# SNES_TST_Sheet4.net
KiCad netlist of a schematic drawn in Altium Designer
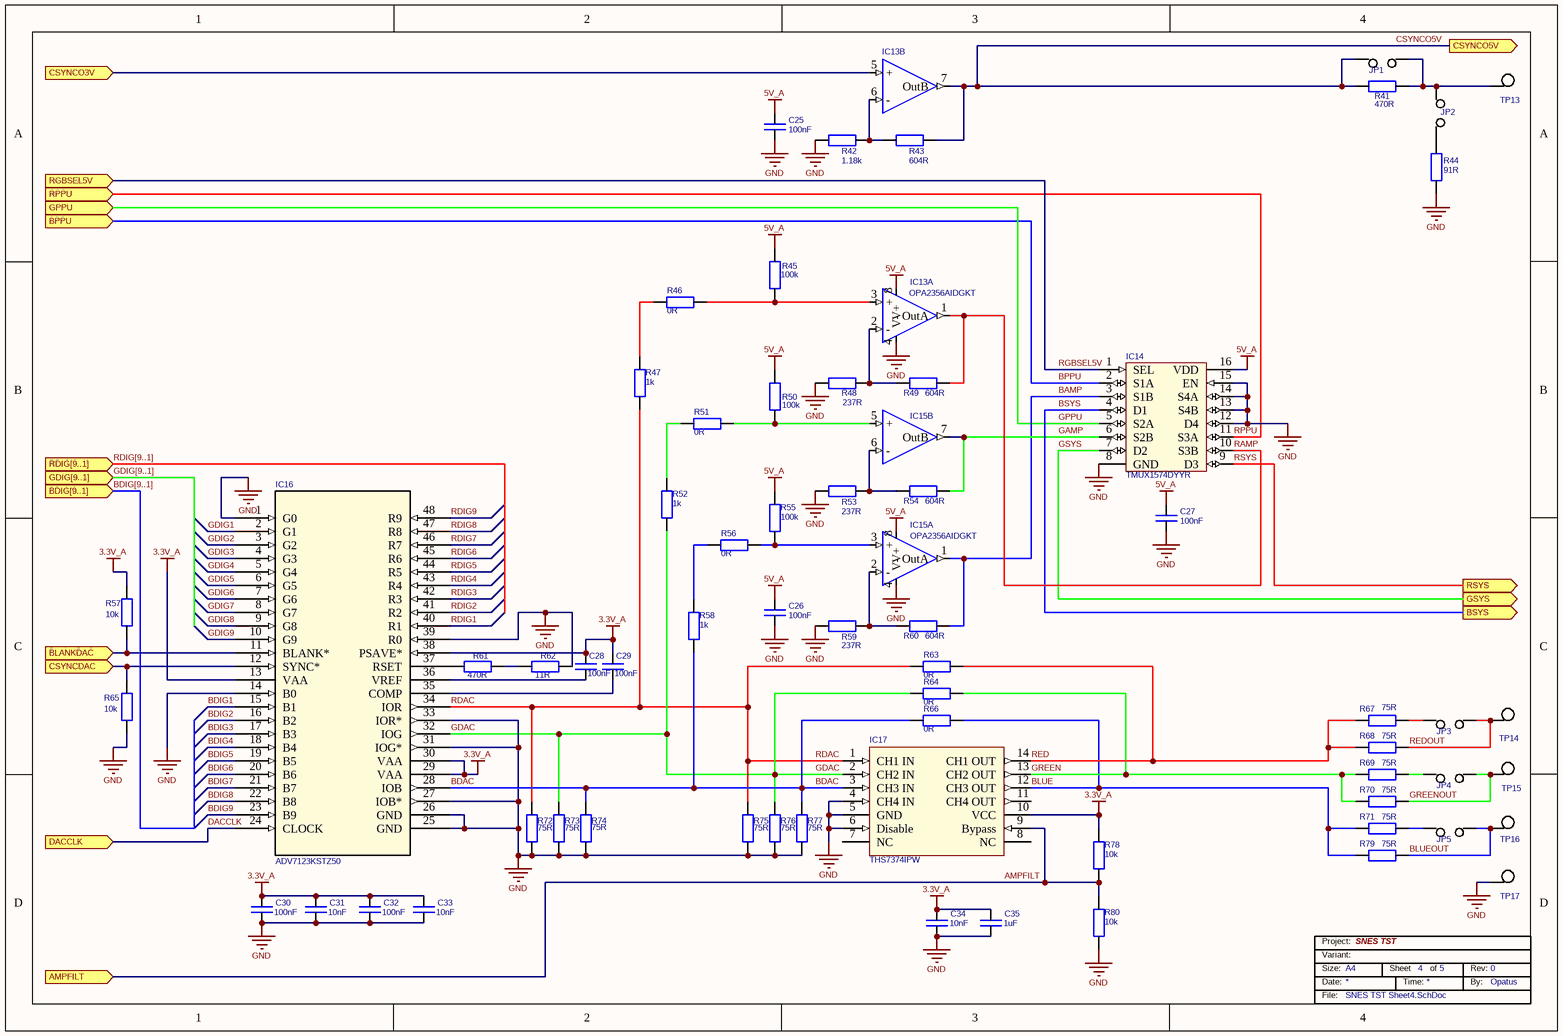
[diagram p0: SNES TST Sheet4.SchDoc]

(export (version "E")
  (design (tool "Eeschema 10.0.6"))
  (components
    (comp (ref "C25")
      (value "100nF")
      (footprint "Cap_0402_Chip")
      (fields
        (field (name "TOLERANCE") "±20%")
        (field (name "Comment") "Ceramic Capacitor 100nF 10V ±20% X7R 0402")
      )
      (libsource (lib "PCB") (part "Capacitor"))
    )
    (comp (ref "C26")
      (value "100nF")
      (footprint "Cap_0402_Chip")
      (fields
        (field (name "TOLERANCE") "±20%")
        (field (name "Comment") "Ceramic Capacitor 100nF 10V ±20% X7R 0402")
      )
      (libsource (lib "PCB") (part "Capacitor"))
    )
    (comp (ref "C27")
      (value "100nF")
      (footprint "Cap_0402_Chip")
      (fields
        (field (name "TOLERANCE") "±20%")
        (field (name "Comment") "Ceramic Capacitor 100nF 10V ±20% X7R 0402")
      )
      (libsource (lib "PCB") (part "Capacitor"))
    )
    (comp (ref "C28")
      (value "100nF")
      (footprint "Cap_0402_Chip")
      (fields
        (field (name "TOLERANCE") "±20%")
        (field (name "Comment") "Ceramic Capacitor 100nF 10V ±20% X7R 0402")
      )
      (libsource (lib "PCB") (part "Capacitor"))
    )
    (comp (ref "C29")
      (value "100nF")
      (footprint "Cap_0402_Chip")
      (fields
        (field (name "TOLERANCE") "±20%")
        (field (name "Comment") "Ceramic Capacitor 100nF 10V ±20% X7R 0402")
      )
      (libsource (lib "PCB") (part "Capacitor"))
    )
    (comp (ref "C30")
      (value "100nF")
      (footprint "Cap_0402_Chip")
      (fields
        (field (name "TOLERANCE") "±20%")
        (field (name "Comment") "Ceramic Capacitor 100nF 10V ±20% X7R 0402")
      )
      (libsource (lib "PCB") (part "Capacitor"))
    )
    (comp (ref "C31")
      (value "10nF")
      (footprint "Cap_0402_Chip")
      (fields
        (field (name "TOLERANCE") "±20%")
        (field (name "Comment") "Ceramic Capacitor 10nF 10V ±20% X7R 0402")
      )
      (libsource (lib "PCB") (part "Capacitor"))
    )
    (comp (ref "C32")
      (value "100nF")
      (footprint "Cap_0402_Chip")
      (fields
        (field (name "TOLERANCE") "±20%")
        (field (name "Comment") "Ceramic Capacitor 100nF 10V ±20% X7R 0402")
      )
      (libsource (lib "PCB") (part "Capacitor"))
    )
    (comp (ref "C33")
      (value "10nF")
      (footprint "Cap_0402_Chip")
      (fields
        (field (name "TOLERANCE") "±20%")
        (field (name "Comment") "Ceramic Capacitor 10nF 10V ±20% X7R 0402")
      )
      (libsource (lib "PCB") (part "Capacitor"))
    )
    (comp (ref "C34")
      (value "10nF")
      (footprint "Cap_0402_Chip")
      (fields
        (field (name "TOLERANCE") "±20%")
        (field (name "Comment") "Ceramic Capacitor 10nF 10V ±20% X7R 0402")
      )
      (libsource (lib "PCB") (part "Capacitor"))
    )
    (comp (ref "C35")
      (value "1uF")
      (footprint "Cap_0603_Chip")
      (fields
        (field (name "TOLERANCE") "±20%")
        (field (name "Comment") "Ceramic Capacitor 1uF 10V ±20% X7R 0603")
      )
      (libsource (lib "PCB") (part "Capacitor"))
    )
    (comp (ref "IC13")
      (value "OPA2356")
      (footprint "MSOP8")
      (fields (field (name "MANUFACTURER_PART_NUMBER") "OPA2356AIDGKT"))
      (libsource (lib "PCB") (part "OPA2356"))
    )
    (comp (ref "IC14")
      (value "TMUX1574")
      (footprint "SOT-23THIN16")
      (description "SPDT 4 Ch")
      (fields (field (name "MANUFACTURER_PART_NUMBER") "TMUX1574DYYR"))
      (libsource (lib "PCB") (part "TMUX1574"))
    )
    (comp (ref "IC15")
      (value "OPA2356")
      (footprint "MSOP8")
      (fields (field (name "MANUFACTURER_PART_NUMBER") "OPA2356AIDGKT"))
      (libsource (lib "PCB") (part "OPA2356"))
    )
    (comp (ref "IC16")
      (value "ADV7123")
      (footprint "ST_48_ADI")
      (description "10Bit Video DAC")
      (fields
        (field (name "MANUFACTURER_PART_NUMBER") "ADV7123KSTZ50")
        (field (name "COPYRIGHT") "Copyright (C) 2018 Accelerated Designs. All rights reserved")
      )
      (libsource (lib "PCB") (part "ADV7123KSTZ140"))
    )
    (comp (ref "IC17")
      (value "THS7374")
      (footprint "TSSOP14")
      (fields (field (name "MANUFACTURER_PART_NUMBER") "THS7374IPW"))
      (libsource (lib "PCB") (part "THS7374"))
    )
    (comp (ref "JP1") (value "Jumper") (footprint "Jumper") (libsource (lib "PCB") (part "Jumper")))
    (comp (ref "JP2") (value "Jumper") (footprint "Jumper") (libsource (lib "PCB") (part "Jumper")))
    (comp (ref "JP3") (value "Jumper") (footprint "Jumper") (libsource (lib "PCB") (part "Jumper")))
    (comp (ref "JP4") (value "Jumper") (footprint "Jumper") (libsource (lib "PCB") (part "Jumper")))
    (comp (ref "JP5") (value "Jumper") (footprint "Jumper") (libsource (lib "PCB") (part "Jumper")))
    (comp (ref "R41")
      (value "470R")
      (footprint "Res_0603_Chip")
      (fields (field (name "TOLERANCE") "±1%") (field (name "Comment") "Resistor 470R 0603 ±1%"))
      (libsource (lib "PCB") (part "R"))
    )
    (comp (ref "R42")
      (value "1.18k")
      (footprint "Res_0402_Chip")
      (fields (field (name "TOLERANCE") "±1%") (field (name "Comment") "Resistor 1.18k 0402 ±1%"))
      (libsource (lib "PCB") (part "R"))
    )
    (comp (ref "R43")
      (value "604R")
      (footprint "Res_0402_Chip")
      (fields (field (name "TOLERANCE") "±1%") (field (name "Comment") "Resistor 604R 0402 ±1%"))
      (libsource (lib "") (part "R_2"))
    )
    (comp (ref "R44")
      (value "91R")
      (footprint "Res_0603_Chip")
      (fields (field (name "TOLERANCE") "±1%") (field (name "Comment") "Resistor 91R 0603 ±1%"))
      (libsource (lib "") (part "R_1"))
    )
    (comp (ref "R45")
      (value "100k")
      (footprint "Res_0402_Chip")
      (fields (field (name "TOLERANCE") "±1%") (field (name "Comment") "Resistor 100k 0402 ±1%"))
      (libsource (lib "") (part "R_1"))
    )
    (comp (ref "R46")
      (value "0R")
      (footprint "Res_0402_Chip")
      (fields (field (name "Comment") "Resistor 0R 0402 "))
      (libsource (lib "") (part "R_2"))
    )
    (comp (ref "R47")
      (value "1k")
      (footprint "Res_0402_Chip")
      (fields (field (name "TOLERANCE") "±1%") (field (name "Comment") "Resistor 1k 0402 ±1%"))
      (libsource (lib "") (part "R_3"))
    )
    (comp (ref "R48")
      (value "237R")
      (footprint "Res_0402_Chip")
      (fields (field (name "TOLERANCE") "±1%") (field (name "Comment") "Resistor 237R 0402 ±1%"))
      (libsource (lib "PCB") (part "R"))
    )
    (comp (ref "R49")
      (value "604R")
      (footprint "Res_0402_Chip")
      (fields (field (name "TOLERANCE") "±1%") (field (name "Comment") "Resistor 604R 0402 ±1%"))
      (libsource (lib "PCB") (part "R"))
    )
    (comp (ref "R50")
      (value "100k")
      (footprint "Res_0402_Chip")
      (fields (field (name "TOLERANCE") "±1%") (field (name "Comment") "Resistor 100k 0402 ±1%"))
      (libsource (lib "") (part "R_1"))
    )
    (comp (ref "R51")
      (value "0R")
      (footprint "Res_0402_Chip")
      (fields (field (name "Comment") "Resistor 0R 0402 "))
      (libsource (lib "") (part "R_2"))
    )
    (comp (ref "R52")
      (value "1k")
      (footprint "Res_0402_Chip")
      (fields (field (name "TOLERANCE") "±1%") (field (name "Comment") "Resistor 1k 0402 ±1%"))
      (libsource (lib "") (part "R_3"))
    )
    (comp (ref "R53")
      (value "237R")
      (footprint "Res_0402_Chip")
      (fields (field (name "TOLERANCE") "±1%") (field (name "Comment") "Resistor 237R 0402 ±1%"))
      (libsource (lib "PCB") (part "R"))
    )
    (comp (ref "R54")
      (value "604R")
      (footprint "Res_0402_Chip")
      (fields (field (name "TOLERANCE") "±1%") (field (name "Comment") "Resistor 604R 0402 ±1%"))
      (libsource (lib "") (part "R_2"))
    )
    (comp (ref "R55")
      (value "100k")
      (footprint "Res_0402_Chip")
      (fields (field (name "TOLERANCE") "±1%") (field (name "Comment") "Resistor 100k 0402 ±1%"))
      (libsource (lib "") (part "R_1"))
    )
    (comp (ref "R56")
      (value "0R")
      (footprint "Res_0402_Chip")
      (fields (field (name "Comment") "Resistor 0R 0402 "))
      (libsource (lib "") (part "R_2"))
    )
    (comp (ref "R57")
      (value "10k")
      (footprint "Res_0402_Chip")
      (fields (field (name "TOLERANCE") "±1%") (field (name "Comment") "Resistor 10k 0402 ±1%"))
      (libsource (lib "") (part "R_1"))
    )
    (comp (ref "R58")
      (value "1k")
      (footprint "Res_0402_Chip")
      (fields (field (name "TOLERANCE") "±1%") (field (name "Comment") "Resistor 1k 0402 ±1%"))
      (libsource (lib "") (part "R_3"))
    )
    (comp (ref "R59")
      (value "237R")
      (footprint "Res_0402_Chip")
      (fields (field (name "TOLERANCE") "±1%") (field (name "Comment") "Resistor 237R 0402 ±1%"))
      (libsource (lib "") (part "R_2"))
    )
    (comp (ref "R60")
      (value "604R")
      (footprint "Res_0402_Chip")
      (fields (field (name "TOLERANCE") "±1%") (field (name "Comment") "Resistor 604R 0402 ±1%"))
      (libsource (lib "PCB") (part "R"))
    )
    (comp (ref "R61")
      (value "470R")
      (footprint "Res_0402_Chip")
      (fields (field (name "TOLERANCE") "±1%") (field (name "Comment") "Resistor 470R 0402 ±1%"))
      (libsource (lib "PCB") (part "R"))
    )
    (comp (ref "R62")
      (value "11R")
      (footprint "Res_0402_Chip")
      (fields (field (name "TOLERANCE") "±1%") (field (name "Comment") "Resistor 11R 0402 ±1%"))
      (libsource (lib "PCB") (part "R"))
    )
    (comp (ref "R63")
      (value "0R")
      (footprint "Res_0402_Chip")
      (fields (field (name "Comment") "Resistor 0R 0402 "))
      (libsource (lib "") (part "R_2"))
    )
    (comp (ref "R64")
      (value "0R")
      (footprint "Res_0402_Chip")
      (fields (field (name "Comment") "Resistor 0R 0402 "))
      (libsource (lib "") (part "R_2"))
    )
    (comp (ref "R65")
      (value "10k")
      (footprint "Res_0402_Chip")
      (fields (field (name "TOLERANCE") "±1%") (field (name "Comment") "Resistor 10k 0402 ±1%"))
      (libsource (lib "") (part "R_1"))
    )
    (comp (ref "R66")
      (value "0R")
      (footprint "Res_0402_Chip")
      (fields (field (name "Comment") "Resistor 0R 0402 "))
      (libsource (lib "") (part "R_2"))
    )
    (comp (ref "R67")
      (value "75R")
      (footprint "Res_0603_Chip")
      (fields (field (name "TOLERANCE") "±1%") (field (name "Comment") "Resistor 75R 0603 ±1%"))
      (libsource (lib "PCB") (part "R"))
    )
    (comp (ref "R68")
      (value "75R")
      (footprint "Res_0603_Chip")
      (fields (field (name "TOLERANCE") "±1%") (field (name "Comment") "Resistor 75R 0603 ±1%"))
      (libsource (lib "PCB") (part "R"))
    )
    (comp (ref "R69")
      (value "75R")
      (footprint "Res_0603_Chip")
      (fields (field (name "TOLERANCE") "±1%") (field (name "Comment") "Resistor 75R 0603 ±1%"))
      (libsource (lib "PCB") (part "R"))
    )
    (comp (ref "R70")
      (value "75R")
      (footprint "Res_0603_Chip")
      (fields (field (name "TOLERANCE") "±1%") (field (name "Comment") "Resistor 75R 0603 ±1%"))
      (libsource (lib "PCB") (part "R"))
    )
    (comp (ref "R71")
      (value "75R")
      (footprint "Res_0603_Chip")
      (fields (field (name "TOLERANCE") "±1%") (field (name "Comment") "Resistor 75R 0603 ±1%"))
      (libsource (lib "PCB") (part "R"))
    )
    (comp (ref "R72")
      (value "75R")
      (footprint "Res_0402_Chip")
      (fields (field (name "TOLERANCE") "±1%") (field (name "Comment") "Resistor 75R 0402 ±1%"))
      (libsource (lib "") (part "R_1"))
    )
    (comp (ref "R73")
      (value "75R")
      (footprint "Res_0402_Chip")
      (fields (field (name "TOLERANCE") "±1%") (field (name "Comment") "Resistor 75R 0402 ±1%"))
      (libsource (lib "") (part "R_1"))
    )
    (comp (ref "R74")
      (value "75R")
      (footprint "Res_0402_Chip")
      (fields (field (name "TOLERANCE") "±1%") (field (name "Comment") "Resistor 75R 0402 ±1%"))
      (libsource (lib "") (part "R_1"))
    )
    (comp (ref "R75")
      (value "75R")
      (footprint "Res_0402_Chip")
      (fields (field (name "TOLERANCE") "±1%") (field (name "Comment") "Resistor 75R 0402 ±1%"))
      (libsource (lib "") (part "R_1"))
    )
    (comp (ref "R76")
      (value "75R")
      (footprint "Res_0402_Chip")
      (fields (field (name "TOLERANCE") "±1%") (field (name "Comment") "Resistor 75R 0402 ±1%"))
      (libsource (lib "") (part "R_1"))
    )
    (comp (ref "R77")
      (value "75R")
      (footprint "Res_0402_Chip")
      (fields (field (name "TOLERANCE") "±1%") (field (name "Comment") "Resistor 75R 0402 ±1%"))
      (libsource (lib "") (part "R_1"))
    )
    (comp (ref "R78")
      (value "10k")
      (footprint "Res_0402_Chip")
      (fields (field (name "TOLERANCE") "±1%") (field (name "Comment") "Resistor 10k 0402 ±1%"))
      (libsource (lib "") (part "R_3"))
    )
    (comp (ref "R79")
      (value "75R")
      (footprint "Res_0603_Chip")
      (fields (field (name "TOLERANCE") "±1%") (field (name "Comment") "Resistor 75R 0603 ±1%"))
      (libsource (lib "PCB") (part "R"))
    )
    (comp (ref "R80")
      (value "10k")
      (footprint "Res_0402_Chip")
      (fields (field (name "TOLERANCE") "±1%") (field (name "Comment") "Resistor 10k 0402 ±1%"))
      (libsource (lib "") (part "R_3"))
    )
    (comp (ref "TP13")
      (value "Pin Connector")
      (footprint "Pin Connector Small")
      (libsource (lib "PCB") (part "Pin Connector"))
    )
    (comp (ref "TP14")
      (value "Pin Connector")
      (footprint "Pin Connector Small")
      (libsource (lib "PCB") (part "Pin Connector"))
    )
    (comp (ref "TP15")
      (value "Pin Connector")
      (footprint "Pin Connector Small")
      (libsource (lib "PCB") (part "Pin Connector"))
    )
    (comp (ref "TP16")
      (value "Pin Connector")
      (footprint "Pin Connector Small")
      (libsource (lib "PCB") (part "Pin Connector"))
    )
    (comp (ref "TP17")
      (value "Pin Connector")
      (footprint "Pin Connector Small")
      (libsource (lib "PCB") (part "Pin Connector"))
    )
  )
  (nets
    (net (code "1") (name "/AMPFILT") (class "Default")
      (node (ref "IC17") (pin "9") (pinfunction "Bypass_9") (pintype "input"))
      (node (ref "R78") (pin "2") (pintype "passive"))
      (node (ref "R80") (pin "1") (pintype "passive"))
    )
    (net (code "2") (name "/BAMP") (class "Default")
      (node (ref "IC14") (pin "3") (pinfunction "S1B_3") (pintype "bidirectional"))
      (node (ref "IC15") (pin "1") (pinfunction "OutA_1") (pintype "output"))
      (node (ref "R60") (pin "2") (pintype "passive"))
    )
    (net (code "3") (name "/BDAC") (class "Default")
      (node (ref "IC16") (pin "28") (pinfunction "IOB_28") (pintype "output"))
      (node (ref "IC17") (pin "3") (pinfunction "CH3_IN_3") (pintype "input"))
      (node (ref "R58") (pin "2") (pintype "passive"))
      (node (ref "R66") (pin "2") (pintype "passive"))
      (node (ref "R74") (pin "2") (pintype "passive"))
      (node (ref "R77") (pin "2") (pintype "passive"))
    )
    (net (code "4") (name "/BDIG1") (class "Default")
      (node (ref "IC16") (pin "15") (pinfunction "B1_15") (pintype "input"))
    )
    (net (code "5") (name "/BDIG2") (class "Default")
      (node (ref "IC16") (pin "16") (pinfunction "B2_16") (pintype "input"))
    )
    (net (code "6") (name "/BDIG3") (class "Default")
      (node (ref "IC16") (pin "17") (pinfunction "B3_17") (pintype "input"))
    )
    (net (code "7") (name "/BDIG4") (class "Default")
      (node (ref "IC16") (pin "18") (pinfunction "B4_18") (pintype "input"))
    )
    (net (code "8") (name "/BDIG5") (class "Default")
      (node (ref "IC16") (pin "19") (pinfunction "B5_19") (pintype "input"))
    )
    (net (code "9") (name "/BDIG6") (class "Default")
      (node (ref "IC16") (pin "20") (pinfunction "B6_20") (pintype "input"))
    )
    (net (code "10") (name "/BDIG7") (class "Default")
      (node (ref "IC16") (pin "21") (pinfunction "B7_21") (pintype "input"))
    )
    (net (code "11") (name "/BDIG8") (class "Default")
      (node (ref "IC16") (pin "22") (pinfunction "B8_22") (pintype "input"))
    )
    (net (code "12") (name "/BDIG9") (class "Default")
      (node (ref "IC16") (pin "23") (pinfunction "B9_23") (pintype "input"))
    )
    (net (code "14") (name "/BLANKDAC") (class "Default")
      (node (ref "IC16") (pin "11") (pinfunction "BLANK*_11") (pintype "input"))
      (node (ref "R57") (pin "1") (pintype "passive"))
    )
    (net (code "15") (name "/BLUE") (class "Default")
      (node (ref "IC17") (pin "12") (pinfunction "CH3_OUT_12") (pintype "output"))
      (node (ref "R66") (pin "1") (pintype "passive"))
      (node (ref "R71") (pin "1") (pintype "passive"))
      (node (ref "R79") (pin "1") (pintype "passive"))
    )
    (net (code "16") (name "/BLUEOUT") (class "Default")
      (node (ref "JP5") (pin "1") (pinfunction "0_1") (pintype "passive"))
      (node (ref "R79") (pin "2") (pintype "passive"))
      (node (ref "TP16") (pin "1") (pinfunction "0_1") (pintype "passive"))
    )
    (net (code "17") (name "/BPPU") (class "Default")
      (node (ref "IC14") (pin "2") (pinfunction "S1A_2") (pintype "bidirectional"))
    )
    (net (code "18") (name "/BSYS") (class "Default")
      (node (ref "IC14") (pin "4") (pinfunction "D1_4") (pintype "bidirectional"))
    )
    (net (code "19") (name "/CSYNCDAC") (class "Default")
      (node (ref "IC16") (pin "12") (pinfunction "SYNC*_12") (pintype "input"))
      (node (ref "R65") (pin "2") (pintype "passive"))
    )
    (net (code "20") (name "/CSYNCO3V") (class "Default")
      (node (ref "IC13") (pin "5") (pinfunction "+_5") (pintype "input"))
    )
    (net (code "21") (name "/CSYNCO5V") (class "Default")
      (node (ref "IC13") (pin "7") (pinfunction "OutB_7") (pintype "output"))
      (node (ref "JP1") (pin "2") (pinfunction "0_2") (pintype "passive"))
      (node (ref "R41") (pin "1") (pintype "passive"))
      (node (ref "R43") (pin "1") (pintype "passive"))
    )
    (net (code "22") (name "/DACCLK") (class "Default")
      (node (ref "IC16") (pin "24") (pinfunction "CLOCK_24") (pintype "input"))
    )
    (net (code "23") (name "/GAMP") (class "Default")
      (node (ref "IC14") (pin "6") (pinfunction "S2B_6") (pintype "bidirectional"))
      (node (ref "IC15") (pin "7") (pinfunction "OutB_7") (pintype "output"))
      (node (ref "R54") (pin "1") (pintype "passive"))
    )
    (net (code "24") (name "/GDAC") (class "Default")
      (node (ref "IC16") (pin "32") (pinfunction "IOG_32") (pintype "output"))
      (node (ref "IC17") (pin "2") (pinfunction "CH2_IN_2") (pintype "input"))
      (node (ref "R52") (pin "2") (pintype "passive"))
      (node (ref "R64") (pin "2") (pintype "passive"))
      (node (ref "R73") (pin "2") (pintype "passive"))
      (node (ref "R76") (pin "2") (pintype "passive"))
    )
    (net (code "25") (name "/GDIG1") (class "Default")
      (node (ref "IC16") (pin "2") (pinfunction "G1_2") (pintype "input"))
    )
    (net (code "26") (name "/GDIG2") (class "Default")
      (node (ref "IC16") (pin "3") (pinfunction "G2_3") (pintype "input"))
    )
    (net (code "27") (name "/GDIG3") (class "Default")
      (node (ref "IC16") (pin "4") (pinfunction "G3_4") (pintype "input"))
    )
    (net (code "28") (name "/GDIG4") (class "Default")
      (node (ref "IC16") (pin "5") (pinfunction "G4_5") (pintype "input"))
    )
    (net (code "29") (name "/GDIG5") (class "Default")
      (node (ref "IC16") (pin "6") (pinfunction "G5_6") (pintype "input"))
    )
    (net (code "30") (name "/GDIG6") (class "Default")
      (node (ref "IC16") (pin "7") (pinfunction "G6_7") (pintype "input"))
    )
    (net (code "31") (name "/GDIG7") (class "Default")
      (node (ref "IC16") (pin "8") (pinfunction "G7_8") (pintype "input"))
    )
    (net (code "32") (name "/GDIG8") (class "Default")
      (node (ref "IC16") (pin "9") (pinfunction "G8_9") (pintype "input"))
    )
    (net (code "33") (name "/GDIG9") (class "Default")
      (node (ref "IC16") (pin "10") (pinfunction "G9_10") (pintype "input"))
    )
    (net (code "35") (name "/GPPU") (class "Default")
      (node (ref "IC14") (pin "5") (pinfunction "S2A_5") (pintype "bidirectional"))
    )
    (net (code "36") (name "/GREEN") (class "Default")
      (node (ref "IC17") (pin "13") (pinfunction "CH2_OUT_13") (pintype "output"))
      (node (ref "R64") (pin "1") (pintype "passive"))
      (node (ref "R69") (pin "1") (pintype "passive"))
      (node (ref "R70") (pin "1") (pintype "passive"))
    )
    (net (code "37") (name "/GREENOUT") (class "Default")
      (node (ref "JP4") (pin "1") (pinfunction "0_1") (pintype "passive"))
      (node (ref "R70") (pin "2") (pintype "passive"))
      (node (ref "TP15") (pin "1") (pinfunction "0_1") (pintype "passive"))
    )
    (net (code "38") (name "/GSYS") (class "Default")
      (node (ref "IC14") (pin "7") (pinfunction "D2_7") (pintype "bidirectional"))
    )
    (net (code "39") (name "/RAMP") (class "Default")
      (node (ref "IC13") (pin "1") (pinfunction "OutA_1") (pintype "output"))
      (node (ref "IC14") (pin "10") (pinfunction "S3B_10") (pintype "bidirectional"))
      (node (ref "R49") (pin "2") (pintype "passive"))
    )
    (net (code "40") (name "/RDAC") (class "Default")
      (node (ref "IC16") (pin "34") (pinfunction "IOR_34") (pintype "output"))
      (node (ref "IC17") (pin "1") (pinfunction "CH1_IN_1") (pintype "input"))
      (node (ref "R47") (pin "2") (pintype "passive"))
      (node (ref "R63") (pin "2") (pintype "passive"))
      (node (ref "R72") (pin "2") (pintype "passive"))
      (node (ref "R75") (pin "2") (pintype "passive"))
    )
    (net (code "41") (name "/RDIG1") (class "Default")
      (node (ref "IC16") (pin "40") (pinfunction "R1_40") (pintype "input"))
    )
    (net (code "42") (name "/RDIG2") (class "Default")
      (node (ref "IC16") (pin "41") (pinfunction "R2_41") (pintype "input"))
    )
    (net (code "43") (name "/RDIG3") (class "Default")
      (node (ref "IC16") (pin "42") (pinfunction "R3_42") (pintype "input"))
    )
    (net (code "44") (name "/RDIG4") (class "Default")
      (node (ref "IC16") (pin "43") (pinfunction "R4_43") (pintype "input"))
    )
    (net (code "45") (name "/RDIG5") (class "Default")
      (node (ref "IC16") (pin "44") (pinfunction "R5_44") (pintype "input"))
    )
    (net (code "46") (name "/RDIG6") (class "Default")
      (node (ref "IC16") (pin "45") (pinfunction "R6_45") (pintype "input"))
    )
    (net (code "47") (name "/RDIG7") (class "Default")
      (node (ref "IC16") (pin "46") (pinfunction "R7_46") (pintype "input"))
    )
    (net (code "48") (name "/RDIG8") (class "Default")
      (node (ref "IC16") (pin "47") (pinfunction "R8_47") (pintype "input"))
    )
    (net (code "49") (name "/RDIG9") (class "Default")
      (node (ref "IC16") (pin "48") (pinfunction "R9_48") (pintype "input"))
    )
    (net (code "51") (name "/RED") (class "Default")
      (node (ref "IC17") (pin "14") (pinfunction "CH1_OUT_14") (pintype "output"))
      (node (ref "R63") (pin "1") (pintype "passive"))
      (node (ref "R67") (pin "1") (pintype "passive"))
      (node (ref "R68") (pin "1") (pintype "passive"))
    )
    (net (code "52") (name "/REDOUT") (class "Default")
      (node (ref "JP3") (pin "1") (pinfunction "0_1") (pintype "passive"))
      (node (ref "R68") (pin "2") (pintype "passive"))
      (node (ref "TP14") (pin "1") (pinfunction "0_1") (pintype "passive"))
    )
    (net (code "53") (name "/RGBSEL5V") (class "Default")
      (node (ref "IC14") (pin "1") (pinfunction "SEL_1") (pintype "input"))
    )
    (net (code "54") (name "/RPPU") (class "Default")
      (node (ref "IC14") (pin "11") (pinfunction "S3A_11") (pintype "bidirectional"))
    )
    (net (code "55") (name "/RSYS") (class "Default")
      (node (ref "IC14") (pin "9") (pinfunction "D3_9") (pintype "bidirectional"))
    )
    (net (code "56") (name "3.3V_A") (class "Default")
      (node (ref "C28") (pin "1") (pintype "passive"))
      (node (ref "C29") (pin "1") (pintype "passive"))
      (node (ref "C30") (pin "2") (pintype "passive"))
      (node (ref "C31") (pin "2") (pintype "passive"))
      (node (ref "C32") (pin "2") (pintype "passive"))
      (node (ref "C33") (pin "2") (pintype "passive"))
      (node (ref "C34") (pin "2") (pintype "passive"))
      (node (ref "C35") (pin "2") (pintype "passive"))
      (node (ref "IC16") (pin "13") (pinfunction "VAA_13") (pintype "power_in"))
      (node (ref "IC16") (pin "29") (pinfunction "VAA_29") (pintype "power_in"))
      (node (ref "IC16") (pin "30") (pinfunction "VAA_30") (pintype "power_in"))
      (node (ref "IC16") (pin "38") (pinfunction "PSAVE*_38") (pintype "input"))
      (node (ref "IC17") (pin "10") (pinfunction "VCC_10") (pintype "power_in"))
      (node (ref "R57") (pin "2") (pintype "passive"))
      (node (ref "R78") (pin "1") (pintype "passive"))
    )
    (net (code "57") (name "5V_A") (class "Default")
      (node (ref "C25") (pin "1") (pintype "passive"))
      (node (ref "C26") (pin "1") (pintype "passive"))
      (node (ref "C27") (pin "1") (pintype "passive"))
      (node (ref "IC13") (pin "8") (pinfunction "V+_8") (pintype "power_in"))
      (node (ref "IC14") (pin "16") (pinfunction "VDD_16") (pintype "power_in"))
      (node (ref "IC15") (pin "8") (pinfunction "V+_8") (pintype "power_in"))
      (node (ref "R45") (pin "2") (pintype "passive"))
      (node (ref "R50") (pin "2") (pintype "passive"))
      (node (ref "R55") (pin "2") (pintype "passive"))
    )
    (net (code "58") (name "GND") (class "Default")
      (node (ref "C25") (pin "2") (pintype "passive"))
      (node (ref "C26") (pin "2") (pintype "passive"))
      (node (ref "C27") (pin "2") (pintype "passive"))
      (node (ref "C30") (pin "1") (pintype "passive"))
      (node (ref "C31") (pin "1") (pintype "passive"))
      (node (ref "C32") (pin "1") (pintype "passive"))
      (node (ref "C33") (pin "1") (pintype "passive"))
      (node (ref "C34") (pin "1") (pintype "passive"))
      (node (ref "C35") (pin "1") (pintype "passive"))
      (node (ref "IC13") (pin "4") (pinfunction "V-_4") (pintype "power_in"))
      (node (ref "IC14") (pin "12") (pinfunction "D4_12") (pintype "bidirectional"))
      (node (ref "IC14") (pin "13") (pinfunction "S4B_13") (pintype "bidirectional"))
      (node (ref "IC14") (pin "14") (pinfunction "S4A_14") (pintype "bidirectional"))
      (node (ref "IC14") (pin "15") (pinfunction "EN_15") (pintype "input"))
      (node (ref "IC14") (pin "8") (pinfunction "GND_8") (pintype "power_in"))
      (node (ref "IC15") (pin "4") (pinfunction "V-_4") (pintype "power_in"))
      (node (ref "IC16") (pin "1") (pinfunction "G0_1") (pintype "input"))
      (node (ref "IC16") (pin "14") (pinfunction "B0_14") (pintype "input"))
      (node (ref "IC16") (pin "25") (pinfunction "GND_25") (pintype "power_in"))
      (node (ref "IC16") (pin "26") (pinfunction "GND_26") (pintype "power_in"))
      (node (ref "IC16") (pin "27") (pinfunction "IOB*_27") (pintype "output"))
      (node (ref "IC16") (pin "31") (pinfunction "IOG*_31") (pintype "output"))
      (node (ref "IC16") (pin "33") (pinfunction "IOR*_33") (pintype "output"))
      (node (ref "IC16") (pin "39") (pinfunction "R0_39") (pintype "input"))
      (node (ref "IC17") (pin "4") (pinfunction "CH4_IN_4") (pintype "input"))
      (node (ref "IC17") (pin "5") (pinfunction "GND_5") (pintype "power_in"))
      (node (ref "IC17") (pin "6") (pinfunction "Disable_6") (pintype "input"))
      (node (ref "R42") (pin "1") (pintype "passive"))
      (node (ref "R44") (pin "1") (pintype "passive"))
      (node (ref "R48") (pin "1") (pintype "passive"))
      (node (ref "R53") (pin "1") (pintype "passive"))
      (node (ref "R59") (pin "2") (pintype "passive"))
      (node (ref "R62") (pin "2") (pintype "passive"))
      (node (ref "R65") (pin "1") (pintype "passive"))
      (node (ref "R72") (pin "1") (pintype "passive"))
      (node (ref "R73") (pin "1") (pintype "passive"))
      (node (ref "R74") (pin "1") (pintype "passive"))
      (node (ref "R75") (pin "1") (pintype "passive"))
      (node (ref "R76") (pin "1") (pintype "passive"))
      (node (ref "R77") (pin "1") (pintype "passive"))
      (node (ref "R80") (pin "2") (pintype "passive"))
      (node (ref "TP17") (pin "1") (pinfunction "0_1") (pintype "passive"))
    )
    (net (code "59") (name "Net-(IC13A-+)") (class "Default")
      (node (ref "IC13") (pin "3") (pinfunction "+_3") (pintype "input"))
      (node (ref "R45") (pin "1") (pintype "passive"))
      (node (ref "R46") (pin "1") (pintype "passive"))
    )
    (net (code "60") (name "Net-(IC13A--)") (class "Default")
      (node (ref "IC13") (pin "2") (pinfunction "-_2") (pintype "input"))
      (node (ref "R48") (pin "2") (pintype "passive"))
      (node (ref "R49") (pin "1") (pintype "passive"))
    )
    (net (code "61") (name "Net-(IC13B--)") (class "Default")
      (node (ref "IC13") (pin "6") (pinfunction "-_6") (pintype "input"))
      (node (ref "R42") (pin "2") (pintype "passive"))
      (node (ref "R43") (pin "2") (pintype "passive"))
    )
    (net (code "62") (name "Net-(IC15A-+)") (class "Default")
      (node (ref "IC15") (pin "3") (pinfunction "+_3") (pintype "input"))
      (node (ref "R55") (pin "1") (pintype "passive"))
      (node (ref "R56") (pin "1") (pintype "passive"))
    )
    (net (code "63") (name "Net-(IC15A--)") (class "Default")
      (node (ref "IC15") (pin "2") (pinfunction "-_2") (pintype "input"))
      (node (ref "R59") (pin "1") (pintype "passive"))
      (node (ref "R60") (pin "1") (pintype "passive"))
    )
    (net (code "64") (name "Net-(IC15B-+)") (class "Default")
      (node (ref "IC15") (pin "5") (pinfunction "+_5") (pintype "input"))
      (node (ref "R50") (pin "1") (pintype "passive"))
      (node (ref "R51") (pin "1") (pintype "passive"))
    )
    (net (code "65") (name "Net-(IC15B--)") (class "Default")
      (node (ref "IC15") (pin "6") (pinfunction "-_6") (pintype "input"))
      (node (ref "R53") (pin "2") (pintype "passive"))
      (node (ref "R54") (pin "2") (pintype "passive"))
    )
    (net (code "66") (name "Net-(IC16-COMP)") (class "Default")
      (node (ref "C29") (pin "2") (pintype "passive"))
      (node (ref "IC16") (pin "35") (pinfunction "COMP_35") (pintype "passive"))
    )
    (net (code "67") (name "Net-(IC16-RSET)") (class "Default")
      (node (ref "IC16") (pin "37") (pinfunction "RSET_37") (pintype "passive"))
      (node (ref "R61") (pin "1") (pintype "passive"))
    )
    (net (code "68") (name "Net-(IC16-VREF)") (class "Default")
      (node (ref "C28") (pin "2") (pintype "passive"))
      (node (ref "IC16") (pin "36") (pinfunction "VREF_36") (pintype "passive"))
    )
    (net (code "69") (name "Net-(JP2-0-Pad2)") (class "Default")
      (node (ref "JP2") (pin "2") (pinfunction "0_2") (pintype "passive"))
      (node (ref "R44") (pin "2") (pintype "passive"))
    )
    (net (code "70") (name "Net-(JP3-0-Pad2)") (class "Default")
      (node (ref "JP3") (pin "2") (pinfunction "0_2") (pintype "passive"))
      (node (ref "R67") (pin "2") (pintype "passive"))
    )
    (net (code "71") (name "Net-(JP4-0-Pad2)") (class "Default")
      (node (ref "JP4") (pin "2") (pinfunction "0_2") (pintype "passive"))
      (node (ref "R69") (pin "2") (pintype "passive"))
    )
    (net (code "72") (name "Net-(JP5-0-Pad2)") (class "Default")
      (node (ref "JP5") (pin "2") (pinfunction "0_2") (pintype "passive"))
      (node (ref "R71") (pin "2") (pintype "passive"))
    )
    (net (code "73") (name "Net-(R46-Pad2)") (class "Default")
      (node (ref "R46") (pin "2") (pintype "passive"))
      (node (ref "R47") (pin "1") (pintype "passive"))
    )
    (net (code "74") (name "Net-(R51-Pad2)") (class "Default")
      (node (ref "R51") (pin "2") (pintype "passive"))
      (node (ref "R52") (pin "1") (pintype "passive"))
    )
    (net (code "75") (name "Net-(R56-Pad2)") (class "Default")
      (node (ref "R56") (pin "2") (pintype "passive"))
      (node (ref "R58") (pin "1") (pintype "passive"))
    )
    (net (code "76") (name "Net-(R61-Pad2)") (class "Default")
      (node (ref "R61") (pin "2") (pintype "passive"))
      (node (ref "R62") (pin "1") (pintype "passive"))
    )
    (net (code "77") (name "Net-(TP13-0)") (class "Default")
      (node (ref "JP1") (pin "1") (pinfunction "0_1") (pintype "passive"))
      (node (ref "JP2") (pin "1") (pinfunction "0_1") (pintype "passive"))
      (node (ref "R41") (pin "2") (pintype "passive"))
      (node (ref "TP13") (pin "1") (pinfunction "0_1") (pintype "passive"))
    )
    (net (code "78") (name "unconnected-(IC17-CH4_OUT-Pad11)") (class "Default")
      (node (ref "IC17") (pin "11") (pinfunction "CH4_OUT_11") (pintype "output"))
    )
    (net (code "79") (name "unconnected-(IC17-NC-Pad7)") (class "Default")
      (node (ref "IC17") (pin "7") (pinfunction "NC_7") (pintype "passive"))
    )
    (net (code "80") (name "unconnected-(IC17-NC-Pad8)") (class "Default")
      (node (ref "IC17") (pin "8") (pinfunction "NC_8") (pintype "passive"))
    )
  )
)
